# IRComms.net
KiCad netlist of a schematic drawn in Altium Designer
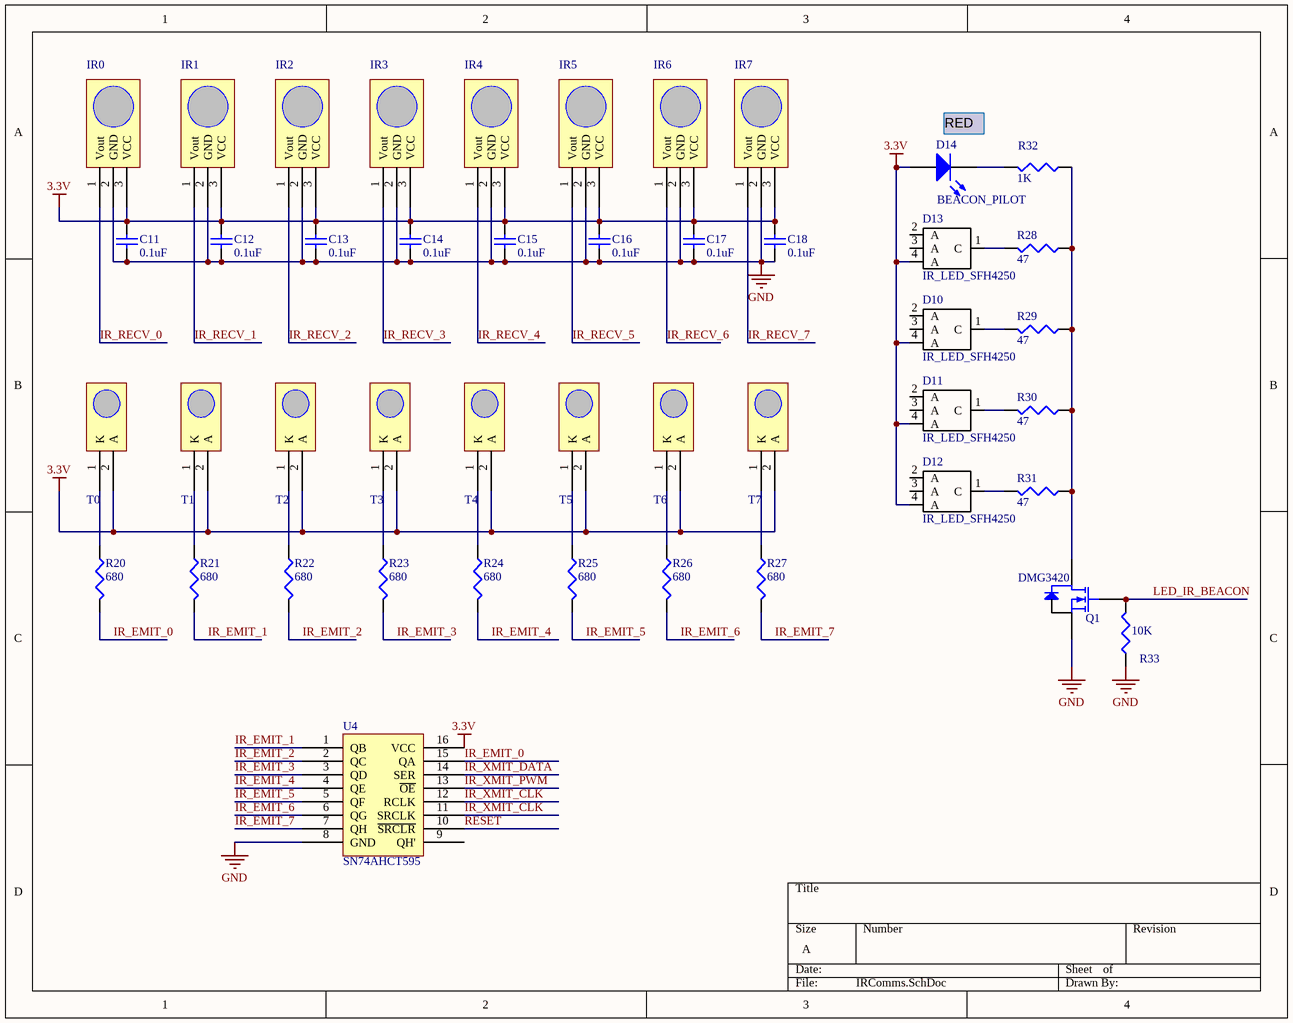
[diagram p0: IRComms.SchDoc]

(export (version "E")
  (design (tool "Eeschema 10.0.6"))
  (components
    (comp (ref "C11")
      (value "0.1uF")
      (footprint "CAPC1005L")
      (description "Capacitor (Semiconductor SIM Model)")
      (fields
        (field (name "PART NUMBER") "C1005X5R1A104M050BA")
        (field (name "MANUFACTURER") "TDK")
        (field (name "PUBLISHER") "Altium Limited")
      )
      (libsource (lib "Miscellaneous Devices") (part "Cap Semi"))
    )
    (comp (ref "C12")
      (value "0.1uF")
      (footprint "CAPC1005L")
      (description "Capacitor (Semiconductor SIM Model)")
      (fields
        (field (name "PART NUMBER") "C1005X5R1A104M050BA")
        (field (name "MANUFACTURER") "TDK")
        (field (name "PUBLISHER") "Altium Limited")
      )
      (libsource (lib "Miscellaneous Devices") (part "Cap Semi"))
    )
    (comp (ref "C13")
      (value "0.1uF")
      (footprint "CAPC1005L")
      (description "Capacitor (Semiconductor SIM Model)")
      (fields
        (field (name "PART NUMBER") "C1005X5R1A104M050BA")
        (field (name "MANUFACTURER") "TDK")
        (field (name "PUBLISHER") "Altium Limited")
      )
      (libsource (lib "Miscellaneous Devices") (part "Cap Semi"))
    )
    (comp (ref "C14")
      (value "0.1uF")
      (footprint "CAPC1005L")
      (description "Capacitor (Semiconductor SIM Model)")
      (fields
        (field (name "PART NUMBER") "C1005X5R1A104M050BA")
        (field (name "MANUFACTURER") "TDK")
        (field (name "PUBLISHER") "Altium Limited")
      )
      (libsource (lib "Miscellaneous Devices") (part "Cap Semi"))
    )
    (comp (ref "C15")
      (value "0.1uF")
      (footprint "CAPC1005L")
      (description "Capacitor (Semiconductor SIM Model)")
      (fields
        (field (name "PART NUMBER") "C1005X5R1A104M050BA")
        (field (name "MANUFACTURER") "TDK")
        (field (name "PUBLISHER") "Altium Limited")
      )
      (libsource (lib "Miscellaneous Devices") (part "Cap Semi"))
    )
    (comp (ref "C16")
      (value "0.1uF")
      (footprint "CAPC1005L")
      (description "Capacitor (Semiconductor SIM Model)")
      (fields
        (field (name "PART NUMBER") "C1005X5R1A104M050BA")
        (field (name "MANUFACTURER") "TDK")
        (field (name "PUBLISHER") "Altium Limited")
      )
      (libsource (lib "Miscellaneous Devices") (part "Cap Semi"))
    )
    (comp (ref "C17")
      (value "0.1uF")
      (footprint "CAPC1005L")
      (description "Capacitor (Semiconductor SIM Model)")
      (fields
        (field (name "PART NUMBER") "C1005X5R1A104M050BA")
        (field (name "MANUFACTURER") "TDK")
        (field (name "PUBLISHER") "Altium Limited")
      )
      (libsource (lib "Miscellaneous Devices") (part "Cap Semi"))
    )
    (comp (ref "C18")
      (value "0.1uF")
      (footprint "CAPC1005L")
      (description "Capacitor (Semiconductor SIM Model)")
      (fields
        (field (name "PART NUMBER") "C1005X5R1A104M050BA")
        (field (name "MANUFACTURER") "TDK")
        (field (name "PUBLISHER") "Altium Limited")
      )
      (libsource (lib "Miscellaneous Devices") (part "Cap Semi"))
    )
    (comp (ref "D10")
      (value "IR_LED_SFH4250")
      (footprint "IR_LED_SFH4250")
      (fields (field (name "PART NUMBER") "SFH 4283-Z") (field (name "MANUFACTURER") "Osram"))
      (libsource (lib "mrone") (part "IR_LED_SFH4250"))
    )
    (comp (ref "D11")
      (value "IR_LED_SFH4250")
      (footprint "IR_LED_SFH4250")
      (fields (field (name "PART NUMBER") "SFH 4283-Z") (field (name "MANUFACTURER") "Osram"))
      (libsource (lib "mrone") (part "IR_LED_SFH4250"))
    )
    (comp (ref "D12")
      (value "IR_LED_SFH4250")
      (footprint "IR_LED_SFH4250")
      (fields (field (name "PART NUMBER") "SFH 4283-Z") (field (name "MANUFACTURER") "Osram"))
      (libsource (lib "mrone") (part "IR_LED_SFH4250"))
    )
    (comp (ref "D13")
      (value "IR_LED_SFH4250")
      (footprint "IR_LED_SFH4250")
      (fields (field (name "PART NUMBER") "SFH 4283-Z") (field (name "MANUFACTURER") "Osram"))
      (libsource (lib "mrone") (part "IR_LED_SFH4250"))
    )
    (comp (ref "D14")
      (value "BEACON_PILOT")
      (footprint "SurfaceMount(603)")
      (fields (field (name "PART NUMBER") "LS Q976-NR-1") (field (name "MANUFACTURER") "Osram"))
      (libsource (lib "mrone") (part "LED"))
    )
    (comp (ref "IR0")
      (value "GP1UX31QS")
      (footprint "GP1UX31QS")
      (fields
        (field (name "PART NUMBER") "GP1UX311QS")
        (field (name "MANUFACTURER") "Sharp Microelectronics")
      )
      (libsource (lib "mrone") (part "GP1UX31QS"))
    )
    (comp (ref "IR1")
      (value "GP1UX31QS")
      (footprint "GP1UX31QS")
      (fields
        (field (name "PART NUMBER") "GP1UX311QS")
        (field (name "MANUFACTURER") "Sharp Microelectronics")
      )
      (libsource (lib "mrone") (part "GP1UX31QS"))
    )
    (comp (ref "IR2")
      (value "GP1UX31QS")
      (footprint "GP1UX31QS")
      (fields
        (field (name "PART NUMBER") "GP1UX311QS")
        (field (name "MANUFACTURER") "Sharp Microelectronics")
      )
      (libsource (lib "mrone") (part "GP1UX31QS"))
    )
    (comp (ref "IR3")
      (value "GP1UX31QS")
      (footprint "GP1UX31QS")
      (fields
        (field (name "PART NUMBER") "GP1UX311QS")
        (field (name "MANUFACTURER") "Sharp Microelectronics")
      )
      (libsource (lib "mrone") (part "GP1UX31QS"))
    )
    (comp (ref "IR4")
      (value "GP1UX31QS")
      (footprint "GP1UX31QS")
      (fields
        (field (name "PART NUMBER") "GP1UX311QS")
        (field (name "MANUFACTURER") "Sharp Microelectronics")
      )
      (libsource (lib "mrone") (part "GP1UX31QS"))
    )
    (comp (ref "IR5")
      (value "GP1UX31QS")
      (footprint "GP1UX31QS")
      (fields
        (field (name "PART NUMBER") "GP1UX311QS")
        (field (name "MANUFACTURER") "Sharp Microelectronics")
      )
      (libsource (lib "mrone") (part "GP1UX31QS"))
    )
    (comp (ref "IR6")
      (value "GP1UX31QS")
      (footprint "GP1UX31QS")
      (fields
        (field (name "PART NUMBER") "GP1UX311QS")
        (field (name "MANUFACTURER") "Sharp Microelectronics")
      )
      (libsource (lib "mrone") (part "GP1UX31QS"))
    )
    (comp (ref "IR7")
      (value "GP1UX31QS")
      (footprint "GP1UX31QS")
      (fields
        (field (name "PART NUMBER") "GP1UX311QS")
        (field (name "MANUFACTURER") "Sharp Microelectronics")
      )
      (libsource (lib "mrone") (part "GP1UX31QS"))
    )
    (comp (ref "Q1")
      (value "Mosfet")
      (footprint "SOT-23")
      (fields
        (field (name "MPN") "DMG3420")
        (field (name "PART NUMBER") "DMG3420U-7")
        (field (name "MANUFACTURER") "Diodes")
      )
      (libsource (lib "mrone") (part "Mosfet"))
    )
    (comp (ref "R20")
      (value "680")
      (footprint "RESC1608L")
      (description "Resistor")
      (fields
        (field (name "PART NUMBER") "ERJ-3GEYJ681V")
        (field (name "MANUFACTURER") "Panasonic")
        (field (name "PUBLISHER") "Altium Limited")
      )
      (libsource (lib "Miscellaneous Devices") (part "Res3"))
    )
    (comp (ref "R21")
      (value "680")
      (footprint "RESC1608L")
      (description "Resistor")
      (fields
        (field (name "PART NUMBER") "ERJ-3GEYJ681V")
        (field (name "MANUFACTURER") "Panasonic")
        (field (name "PUBLISHER") "Altium Limited")
      )
      (libsource (lib "Miscellaneous Devices") (part "Res3"))
    )
    (comp (ref "R22")
      (value "680")
      (footprint "RESC1608L")
      (description "Resistor")
      (fields
        (field (name "PART NUMBER") "ERJ-3GEYJ681V")
        (field (name "MANUFACTURER") "Panasonic")
        (field (name "PUBLISHER") "Altium Limited")
      )
      (libsource (lib "Miscellaneous Devices") (part "Res3"))
    )
    (comp (ref "R23")
      (value "680")
      (footprint "RESC1608L")
      (description "Resistor")
      (fields
        (field (name "PART NUMBER") "ERJ-3GEYJ681V")
        (field (name "MANUFACTURER") "Panasonic")
        (field (name "PUBLISHER") "Altium Limited")
      )
      (libsource (lib "Miscellaneous Devices") (part "Res3"))
    )
    (comp (ref "R24")
      (value "680")
      (footprint "RESC1608L")
      (description "Resistor")
      (fields
        (field (name "PART NUMBER") "ERJ-3GEYJ681V")
        (field (name "MANUFACTURER") "Panasonic")
        (field (name "PUBLISHER") "Altium Limited")
      )
      (libsource (lib "Miscellaneous Devices") (part "Res3"))
    )
    (comp (ref "R25")
      (value "680")
      (footprint "RESC1608L")
      (description "Resistor")
      (fields
        (field (name "PART NUMBER") "ERJ-3GEYJ681V")
        (field (name "MANUFACTURER") "Panasonic")
        (field (name "PUBLISHER") "Altium Limited")
      )
      (libsource (lib "Miscellaneous Devices") (part "Res3"))
    )
    (comp (ref "R26")
      (value "680")
      (footprint "RESC1608L")
      (description "Resistor")
      (fields
        (field (name "PART NUMBER") "ERJ-3GEYJ681V")
        (field (name "MANUFACTURER") "Panasonic")
        (field (name "PUBLISHER") "Altium Limited")
      )
      (libsource (lib "Miscellaneous Devices") (part "Res3"))
    )
    (comp (ref "R27")
      (value "680")
      (footprint "RESC1608L")
      (description "Resistor")
      (fields
        (field (name "PART NUMBER") "ERJ-3GEYJ681V")
        (field (name "MANUFACTURER") "Panasonic")
        (field (name "PUBLISHER") "Altium Limited")
      )
      (libsource (lib "Miscellaneous Devices") (part "Res3"))
    )
    (comp (ref "R28")
      (value "47")
      (footprint "RESC1608L")
      (description "Resistor")
      (fields
        (field (name "PART NUMBER") "ERJ-3GEYJ470V")
        (field (name "MANUFACTURER") "Panasonic")
        (field (name "PUBLISHER") "Altium Limited")
      )
      (libsource (lib "Miscellaneous Devices") (part "Res3"))
    )
    (comp (ref "R29")
      (value "47")
      (footprint "RESC1608L")
      (description "Resistor")
      (fields
        (field (name "PART NUMBER") "ERJ-3GEYJ470V")
        (field (name "MANUFACTURER") "Panasonic")
        (field (name "PUBLISHER") "Altium Limited")
      )
      (libsource (lib "Miscellaneous Devices") (part "Res3"))
    )
    (comp (ref "R30")
      (value "47")
      (footprint "RESC1608L")
      (description "Resistor")
      (fields
        (field (name "PART NUMBER") "ERJ-3GEYJ470V")
        (field (name "MANUFACTURER") "Panasonic")
        (field (name "PUBLISHER") "Altium Limited")
      )
      (libsource (lib "Miscellaneous Devices") (part "Res3"))
    )
    (comp (ref "R31")
      (value "47")
      (footprint "RESC1608L")
      (description "Resistor")
      (fields
        (field (name "PART NUMBER") "ERJ-3GEYJ470V")
        (field (name "MANUFACTURER") "Panasonic")
        (field (name "PUBLISHER") "Altium Limited")
      )
      (libsource (lib "Miscellaneous Devices") (part "Res3"))
    )
    (comp (ref "R32")
      (value "1K")
      (footprint "RESC1608L")
      (description "Resistor")
      (fields
        (field (name "PART NUMBER") "SR03-1001")
        (field (name "MANUFACTURER") "Vishay")
        (field (name "PUBLISHER") "Altium Limited")
      )
      (libsource (lib "Miscellaneous Devices") (part "Res3"))
    )
    (comp (ref "R33")
      (value "10K")
      (footprint "RESC1608L")
      (description "Resistor")
      (fields
        (field (name "PART NUMBER") "SR03-1002")
        (field (name "MANUFACTURER") "Vishay")
        (field (name "PUBLISHER") "Altium Limited")
      )
      (libsource (lib "Miscellaneous Devices") (part "Res3"))
    )
    (comp (ref "T0")
      (value "LN54")
      (footprint "LN54")
      (fields (field (name "PART NUMBER") "IRL 80A") (field (name "MANUFACTURER") "Osram"))
      (libsource (lib "mrone") (part "LN54"))
    )
    (comp (ref "T1")
      (value "LN54")
      (footprint "LN54")
      (fields (field (name "PART NUMBER") "IRL 80A") (field (name "MANUFACTURER") "Osram"))
      (libsource (lib "mrone") (part "LN54"))
    )
    (comp (ref "T2")
      (value "LN54")
      (footprint "LN54")
      (fields (field (name "PART NUMBER") "IRL 80A") (field (name "MANUFACTURER") "Osram"))
      (libsource (lib "mrone") (part "LN54"))
    )
    (comp (ref "T3")
      (value "LN54")
      (footprint "LN54")
      (fields (field (name "PART NUMBER") "IRL 80A") (field (name "MANUFACTURER") "Osram"))
      (libsource (lib "mrone") (part "LN54"))
    )
    (comp (ref "T4")
      (value "LN54")
      (footprint "LN54")
      (fields (field (name "PART NUMBER") "IRL 80A") (field (name "MANUFACTURER") "Osram"))
      (libsource (lib "mrone") (part "LN54"))
    )
    (comp (ref "T5")
      (value "LN54")
      (footprint "LN54")
      (fields (field (name "PART NUMBER") "IRL 80A") (field (name "MANUFACTURER") "Osram"))
      (libsource (lib "mrone") (part "LN54"))
    )
    (comp (ref "T6")
      (value "LN54")
      (footprint "LN54")
      (fields (field (name "PART NUMBER") "IRL 80A") (field (name "MANUFACTURER") "Osram"))
      (libsource (lib "mrone") (part "LN54"))
    )
    (comp (ref "T7")
      (value "LN54")
      (footprint "LN54")
      (fields (field (name "PART NUMBER") "IRL 80A") (field (name "MANUFACTURER") "Osram"))
      (libsource (lib "mrone") (part "LN54"))
    )
    (comp (ref "U4")
      (value "SN74AHCT595")
      (footprint "TSSOP-16")
      (description "shift register")
      (fields (field (name "PART NUMBER") "SN74AHCT595PW") (field (name "MANUFACTURER") "TI"))
      (libsource (lib "mrone") (part "SN74AHCT595"))
    )
  )
  (nets
    (net (code "1") (name "/IR_EMIT_0") (class "Default")
      (node (ref "R20") (pin "2") (pinfunction "2_2") (pintype "passive"))
      (node (ref "U4") (pin "15") (pinfunction "QA_15") (pintype "passive"))
    )
    (net (code "2") (name "/IR_EMIT_1") (class "Default")
      (node (ref "R21") (pin "2") (pinfunction "2_2") (pintype "passive"))
      (node (ref "U4") (pin "1") (pinfunction "QB_1") (pintype "passive"))
    )
    (net (code "3") (name "/IR_EMIT_2") (class "Default")
      (node (ref "R22") (pin "2") (pinfunction "2_2") (pintype "passive"))
      (node (ref "U4") (pin "2") (pinfunction "QC_2") (pintype "passive"))
    )
    (net (code "4") (name "/IR_EMIT_3") (class "Default")
      (node (ref "R23") (pin "2") (pinfunction "2_2") (pintype "passive"))
      (node (ref "U4") (pin "3") (pinfunction "QD_3") (pintype "passive"))
    )
    (net (code "5") (name "/IR_EMIT_4") (class "Default")
      (node (ref "R24") (pin "2") (pinfunction "2_2") (pintype "passive"))
      (node (ref "U4") (pin "4") (pinfunction "QE_4") (pintype "passive"))
    )
    (net (code "6") (name "/IR_EMIT_5") (class "Default")
      (node (ref "R25") (pin "2") (pinfunction "2_2") (pintype "passive"))
      (node (ref "U4") (pin "5") (pinfunction "QF_5") (pintype "passive"))
    )
    (net (code "7") (name "/IR_EMIT_6") (class "Default")
      (node (ref "R26") (pin "2") (pinfunction "2_2") (pintype "passive"))
      (node (ref "U4") (pin "6") (pinfunction "QG_6") (pintype "passive"))
    )
    (net (code "8") (name "/IR_EMIT_7") (class "Default")
      (node (ref "R27") (pin "2") (pinfunction "2_2") (pintype "passive"))
      (node (ref "U4") (pin "7") (pinfunction "QH_7") (pintype "passive"))
    )
    (net (code "9") (name "/IR_RECV_0") (class "Default")
      (node (ref "IR0") (pin "1") (pinfunction "Vout_1") (pintype "passive"))
    )
    (net (code "10") (name "/IR_RECV_1") (class "Default")
      (node (ref "IR1") (pin "1") (pinfunction "Vout_1") (pintype "passive"))
    )
    (net (code "11") (name "/IR_RECV_2") (class "Default")
      (node (ref "IR2") (pin "1") (pinfunction "Vout_1") (pintype "passive"))
    )
    (net (code "12") (name "/IR_RECV_3") (class "Default")
      (node (ref "IR3") (pin "1") (pinfunction "Vout_1") (pintype "passive"))
    )
    (net (code "13") (name "/IR_RECV_4") (class "Default")
      (node (ref "IR4") (pin "1") (pinfunction "Vout_1") (pintype "passive"))
    )
    (net (code "14") (name "/IR_RECV_5") (class "Default")
      (node (ref "IR5") (pin "1") (pinfunction "Vout_1") (pintype "passive"))
    )
    (net (code "15") (name "/IR_RECV_6") (class "Default")
      (node (ref "IR6") (pin "1") (pinfunction "Vout_1") (pintype "passive"))
    )
    (net (code "16") (name "/IR_RECV_7") (class "Default")
      (node (ref "IR7") (pin "1") (pinfunction "Vout_1") (pintype "passive"))
    )
    (net (code "17") (name "/IR_XMIT_CLK") (class "Default")
      (node (ref "U4") (pin "11") (pinfunction "SRCLK_11") (pintype "passive"))
      (node (ref "U4") (pin "12") (pinfunction "RCLK_12") (pintype "passive"))
    )
    (net (code "18") (name "/IR_XMIT_DATA") (class "Default")
      (node (ref "U4") (pin "14") (pinfunction "SER_14") (pintype "passive"))
    )
    (net (code "19") (name "/IR_XMIT_PWM") (class "Default")
      (node (ref "U4") (pin "13") (pinfunction "~{OE}_13") (pintype "passive"))
    )
    (net (code "20") (name "/LED_IR_BEACON") (class "Default")
      (node (ref "Q1") (pin "1") (pinfunction "G_1") (pintype "passive"))
      (node (ref "R33") (pin "2") (pinfunction "2_2") (pintype "passive"))
    )
    (net (code "21") (name "/RESET") (class "Default")
      (node (ref "U4") (pin "10") (pinfunction "~{SRCLR}_10") (pintype "passive"))
    )
    (net (code "22") (name "3.3V") (class "Default")
      (node (ref "C11") (pin "2") (pinfunction "2_2") (pintype "passive"))
      (node (ref "C12") (pin "2") (pinfunction "2_2") (pintype "passive"))
      (node (ref "C13") (pin "2") (pinfunction "2_2") (pintype "passive"))
      (node (ref "C14") (pin "2") (pinfunction "2_2") (pintype "passive"))
      (node (ref "C15") (pin "2") (pinfunction "2_2") (pintype "passive"))
      (node (ref "C16") (pin "2") (pinfunction "2_2") (pintype "passive"))
      (node (ref "C17") (pin "2") (pinfunction "2_2") (pintype "passive"))
      (node (ref "C18") (pin "2") (pinfunction "2_2") (pintype "passive"))
      (node (ref "D10") (pin "4") (pinfunction "A_4") (pintype "passive"))
      (node (ref "D11") (pin "4") (pinfunction "A_4") (pintype "passive"))
      (node (ref "D12") (pin "4") (pinfunction "A_4") (pintype "passive"))
      (node (ref "D13") (pin "4") (pinfunction "A_4") (pintype "passive"))
      (node (ref "D14") (pin "1") (pinfunction "A_1") (pintype "passive"))
      (node (ref "IR0") (pin "3") (pinfunction "VCC_3") (pintype "power_in"))
      (node (ref "IR1") (pin "3") (pinfunction "VCC_3") (pintype "power_in"))
      (node (ref "IR2") (pin "3") (pinfunction "VCC_3") (pintype "power_in"))
      (node (ref "IR3") (pin "3") (pinfunction "VCC_3") (pintype "power_in"))
      (node (ref "IR4") (pin "3") (pinfunction "VCC_3") (pintype "power_in"))
      (node (ref "IR5") (pin "3") (pinfunction "VCC_3") (pintype "power_in"))
      (node (ref "IR6") (pin "3") (pinfunction "VCC_3") (pintype "power_in"))
      (node (ref "IR7") (pin "3") (pinfunction "VCC_3") (pintype "power_in"))
      (node (ref "T0") (pin "2") (pinfunction "A_2") (pintype "passive"))
      (node (ref "T1") (pin "2") (pinfunction "A_2") (pintype "passive"))
      (node (ref "T2") (pin "2") (pinfunction "A_2") (pintype "passive"))
      (node (ref "T3") (pin "2") (pinfunction "A_2") (pintype "passive"))
      (node (ref "T4") (pin "2") (pinfunction "A_2") (pintype "passive"))
      (node (ref "T5") (pin "2") (pinfunction "A_2") (pintype "passive"))
      (node (ref "T6") (pin "2") (pinfunction "A_2") (pintype "passive"))
      (node (ref "T7") (pin "2") (pinfunction "A_2") (pintype "passive"))
      (node (ref "U4") (pin "16") (pinfunction "VCC_16") (pintype "passive"))
    )
    (net (code "23") (name "GND") (class "Default")
      (node (ref "C11") (pin "1") (pinfunction "1_1") (pintype "passive"))
      (node (ref "C12") (pin "1") (pinfunction "1_1") (pintype "passive"))
      (node (ref "C13") (pin "1") (pinfunction "1_1") (pintype "passive"))
      (node (ref "C14") (pin "1") (pinfunction "1_1") (pintype "passive"))
      (node (ref "C15") (pin "1") (pinfunction "1_1") (pintype "passive"))
      (node (ref "C16") (pin "1") (pinfunction "1_1") (pintype "passive"))
      (node (ref "C17") (pin "1") (pinfunction "1_1") (pintype "passive"))
      (node (ref "C18") (pin "1") (pinfunction "1_1") (pintype "passive"))
      (node (ref "IR0") (pin "2") (pinfunction "GND_2") (pintype "power_in"))
      (node (ref "IR1") (pin "2") (pinfunction "GND_2") (pintype "power_in"))
      (node (ref "IR2") (pin "2") (pinfunction "GND_2") (pintype "power_in"))
      (node (ref "IR3") (pin "2") (pinfunction "GND_2") (pintype "power_in"))
      (node (ref "IR4") (pin "2") (pinfunction "GND_2") (pintype "power_in"))
      (node (ref "IR5") (pin "2") (pinfunction "GND_2") (pintype "power_in"))
      (node (ref "IR6") (pin "2") (pinfunction "GND_2") (pintype "power_in"))
      (node (ref "IR7") (pin "2") (pinfunction "GND_2") (pintype "power_in"))
      (node (ref "Q1") (pin "2") (pinfunction "S_2") (pintype "passive"))
      (node (ref "R33") (pin "1") (pinfunction "1_1") (pintype "passive"))
      (node (ref "U4") (pin "8") (pinfunction "GND_8") (pintype "passive"))
    )
    (net (code "24") (name "Net-(D10-C)") (class "Default")
      (node (ref "D10") (pin "1") (pinfunction "C_1") (pintype "passive"))
      (node (ref "R29") (pin "2") (pinfunction "2_2") (pintype "passive"))
    )
    (net (code "25") (name "Net-(D11-C)") (class "Default")
      (node (ref "D11") (pin "1") (pinfunction "C_1") (pintype "passive"))
      (node (ref "R30") (pin "2") (pinfunction "2_2") (pintype "passive"))
    )
    (net (code "26") (name "Net-(D12-C)") (class "Default")
      (node (ref "D12") (pin "1") (pinfunction "C_1") (pintype "passive"))
      (node (ref "R31") (pin "2") (pinfunction "2_2") (pintype "passive"))
    )
    (net (code "27") (name "Net-(D13-C)") (class "Default")
      (node (ref "D13") (pin "1") (pinfunction "C_1") (pintype "passive"))
      (node (ref "R28") (pin "2") (pinfunction "2_2") (pintype "passive"))
    )
    (net (code "28") (name "Net-(D14-K)") (class "Default")
      (node (ref "D14") (pin "2") (pinfunction "K_2") (pintype "passive"))
      (node (ref "R32") (pin "2") (pinfunction "2_2") (pintype "passive"))
    )
    (net (code "29") (name "Net-(Q1-D)") (class "Default")
      (node (ref "Q1") (pin "3") (pinfunction "D_3") (pintype "passive"))
      (node (ref "R28") (pin "1") (pinfunction "1_1") (pintype "passive"))
      (node (ref "R29") (pin "1") (pinfunction "1_1") (pintype "passive"))
      (node (ref "R30") (pin "1") (pinfunction "1_1") (pintype "passive"))
      (node (ref "R31") (pin "1") (pinfunction "1_1") (pintype "passive"))
      (node (ref "R32") (pin "1") (pinfunction "1_1") (pintype "passive"))
    )
    (net (code "30") (name "Net-(T0-K)") (class "Default")
      (node (ref "R20") (pin "1") (pinfunction "1_1") (pintype "passive"))
      (node (ref "T0") (pin "1") (pinfunction "K_1") (pintype "passive"))
    )
    (net (code "31") (name "Net-(T1-K)") (class "Default")
      (node (ref "R21") (pin "1") (pinfunction "1_1") (pintype "passive"))
      (node (ref "T1") (pin "1") (pinfunction "K_1") (pintype "passive"))
    )
    (net (code "32") (name "Net-(T2-K)") (class "Default")
      (node (ref "R22") (pin "1") (pinfunction "1_1") (pintype "passive"))
      (node (ref "T2") (pin "1") (pinfunction "K_1") (pintype "passive"))
    )
    (net (code "33") (name "Net-(T3-K)") (class "Default")
      (node (ref "R23") (pin "1") (pinfunction "1_1") (pintype "passive"))
      (node (ref "T3") (pin "1") (pinfunction "K_1") (pintype "passive"))
    )
    (net (code "34") (name "Net-(T4-K)") (class "Default")
      (node (ref "R24") (pin "1") (pinfunction "1_1") (pintype "passive"))
      (node (ref "T4") (pin "1") (pinfunction "K_1") (pintype "passive"))
    )
    (net (code "35") (name "Net-(T5-K)") (class "Default")
      (node (ref "R25") (pin "1") (pinfunction "1_1") (pintype "passive"))
      (node (ref "T5") (pin "1") (pinfunction "K_1") (pintype "passive"))
    )
    (net (code "36") (name "Net-(T6-K)") (class "Default")
      (node (ref "R26") (pin "1") (pinfunction "1_1") (pintype "passive"))
      (node (ref "T6") (pin "1") (pinfunction "K_1") (pintype "passive"))
    )
    (net (code "37") (name "Net-(T7-K)") (class "Default")
      (node (ref "R27") (pin "1") (pinfunction "1_1") (pintype "passive"))
      (node (ref "T7") (pin "1") (pinfunction "K_1") (pintype "passive"))
    )
    (net (code "38") (name "unconnected-(D10-A-Pad2)") (class "Default")
      (node (ref "D10") (pin "2") (pinfunction "A_2") (pintype "passive"))
    )
    (net (code "39") (name "unconnected-(D10-A-Pad3)") (class "Default")
      (node (ref "D10") (pin "3") (pinfunction "A_3") (pintype "passive"))
    )
    (net (code "40") (name "unconnected-(D11-A-Pad2)") (class "Default")
      (node (ref "D11") (pin "2") (pinfunction "A_2") (pintype "passive"))
    )
    (net (code "41") (name "unconnected-(D11-A-Pad3)") (class "Default")
      (node (ref "D11") (pin "3") (pinfunction "A_3") (pintype "passive"))
    )
    (net (code "42") (name "unconnected-(D12-A-Pad2)") (class "Default")
      (node (ref "D12") (pin "2") (pinfunction "A_2") (pintype "passive"))
    )
    (net (code "43") (name "unconnected-(D12-A-Pad3)") (class "Default")
      (node (ref "D12") (pin "3") (pinfunction "A_3") (pintype "passive"))
    )
    (net (code "44") (name "unconnected-(D13-A-Pad2)") (class "Default")
      (node (ref "D13") (pin "2") (pinfunction "A_2") (pintype "passive"))
    )
    (net (code "45") (name "unconnected-(D13-A-Pad3)") (class "Default")
      (node (ref "D13") (pin "3") (pinfunction "A_3") (pintype "passive"))
    )
    (net (code "46") (name "unconnected-(U4-QH'-Pad9)") (class "Default")
      (node (ref "U4") (pin "9") (pinfunction "QH'_9") (pintype "passive"))
    )
  )
)
